# CE_BJTInfineonTSFP-4-1_v1.net
KiCad netlist of a schematic drawn in Altium Designer
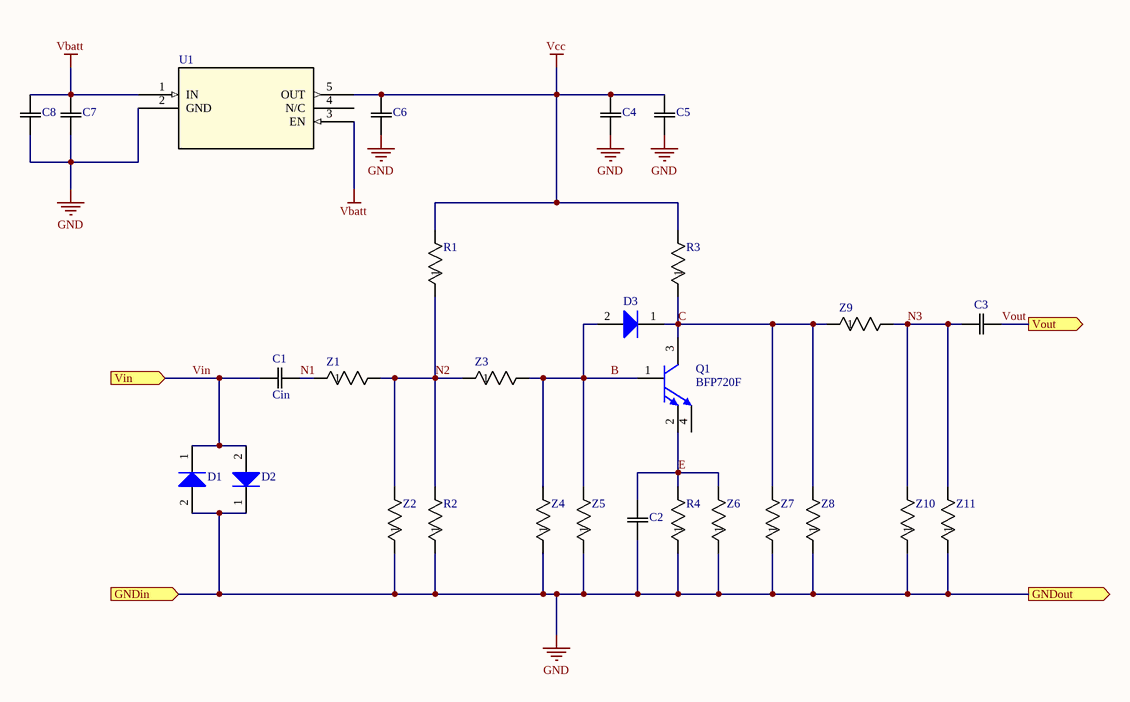
[diagram p0: CE_BJTInfineonTSFP-4-1_v1.SchDoc]

(export (version "E")
  (design (tool "Eeschema 10.0.6"))
  (components
    (comp (ref "C1")
      (value "Cin")
      (footprint "C0201")
      (description "No Description Available")
      (fields
        (field (name "MANUFACTURER_PART_NUMBER") "C0201C270J3GACTU")
        (field (name "COPYRIGHT") "Copyright (C) 2018 Accelerated Designs. All rights reserved")
      )
      (libsource (lib "0201Capacitor_Yageo") (part "C0201C270J3GACTU"))
    )
    (comp (ref "C2")
      (value "~")
      (footprint "C0201")
      (description "No Description Available")
      (fields
        (field (name "MANUFACTURER_PART_NUMBER") "C0201C270J3GACTU")
        (field (name "COPYRIGHT") "Copyright (C) 2018 Accelerated Designs. All rights reserved")
      )
      (libsource (lib "0201Capacitor_Yageo") (part "C0201C270J3GACTU"))
    )
    (comp (ref "C3")
      (value "~")
      (footprint "C0201")
      (description "No Description Available")
      (fields
        (field (name "MANUFACTURER_PART_NUMBER") "C0201C270J3GACTU")
        (field (name "COPYRIGHT") "Copyright (C) 2018 Accelerated Designs. All rights reserved")
      )
      (libsource (lib "0201Capacitor_Yageo") (part "C0201C270J3GACTU"))
    )
    (comp (ref "C4")
      (value "~")
      (footprint "CAP_CBR_0201")
      (description "No Description Available")
      (fields
        (field (name "MANUFACTURER_PART_NUMBER") "CBR02C399C3GAC")
        (field (name "COPYRIGHT") "Copyright (C) 2018 Accelerated Designs. All rights reserved")
      )
      (libsource (lib "0201Capacitor_KEMET") (part "CBR02C399C3GAC"))
    )
    (comp (ref "C5")
      (value "~")
      (footprint "CAP_CBR_0201")
      (description "No Description Available")
      (fields
        (field (name "MANUFACTURER_PART_NUMBER") "CBR02C399C3GAC")
        (field (name "COPYRIGHT") "Copyright (C) 2018 Accelerated Designs. All rights reserved")
      )
      (libsource (lib "0201Capacitor_KEMET") (part "CBR02C399C3GAC"))
    )
    (comp (ref "C6")
      (value "~")
      (footprint "YAG_CC0402")
      (description "No Description Available")
      (fields
        (field (name "MANUFACTURER_PART_NUMBER") "CC0402KRX7R9BB103")
        (field (name "COPYRIGHT") "Copyright (C) 2018 Accelerated Designs. All rights reserved")
      )
      (libsource (lib "0402Capacitor_Yageo") (part "CC0402KRX7R9BB10"))
    )
    (comp (ref "C7")
      (value "~")
      (footprint "YAG_CC0402")
      (description "No Description Available")
      (fields
        (field (name "MANUFACTURER_PART_NUMBER") "CC0402KRX7R9BB103")
        (field (name "COPYRIGHT") "Copyright (C) 2018 Accelerated Designs. All rights reserved")
      )
      (libsource (lib "0402Capacitor_Yageo") (part "CC0402KRX7R9BB10"))
    )
    (comp (ref "C8")
      (value "~")
      (footprint "YAG_CC0402")
      (description "No Description Available")
      (fields
        (field (name "MANUFACTURER_PART_NUMBER") "CC0402KRX7R9BB103")
        (field (name "COPYRIGHT") "Copyright (C) 2018 Accelerated Designs. All rights reserved")
      )
      (libsource (lib "0402Capacitor_Yageo") (part "CC0402KRX7R9BB10"))
    )
    (comp (ref "D1")
      (value "~")
      (footprint "INF-SOD323_V")
      (description "Single Silicon Schottky Diode, 110 mA IF Max, SOD32, Green")
      (fields (field (name "MANUFACTURER") "Infineon") (field (name "PARTNUMBER") "BAT15-03W"))
      (libsource (lib "Infineon_RFSchottkyDiode_SOD323") (part "BAT15-03W"))
    )
    (comp (ref "D2")
      (value "~")
      (footprint "INF-SOD323_V")
      (description "Single Silicon Schottky Diode, 110 mA IF Max, SOD32, Green")
      (fields (field (name "MANUFACTURER") "Infineon") (field (name "PARTNUMBER") "BAT15-03W"))
      (libsource (lib "Infineon_RFSchottkyDiode_SOD323") (part "BAT15-03W"))
    )
    (comp (ref "D3")
      (value "~")
      (footprint "INF-SOD323_V")
      (description "Single Silicon Schottky Diode, 110 mA IF Max, SOD32, Green")
      (fields (field (name "MANUFACTURER") "Infineon") (field (name "PARTNUMBER") "BAT15-03W"))
      (libsource (lib "Infineon_RFSchottkyDiode_SOD323") (part "BAT15-03W"))
    )
    (comp (ref "Q1")
      (value "BFP720F")
      (footprint "INF-TSFP-4-1_V")
      (fields (field (name "MANUFACTURER") "Infineon"))
      (libsource (lib "Infineon_RFBJT_TSFP-4-1") (part "BFP720F"))
    )
    (comp (ref "R1")
      (value "~")
      (footprint "RES_RC0201_P6XP3")
      (description "No Description Available")
      (fields
        (field (name "MANUFACTURER_PART_NUMBER") "RC0201FR-0718KL")
        (field (name "COPYRIGHT") "Copyright (C) 2018 Accelerated Designs. All rights reserved")
      )
      (libsource (lib "0201Resistor_Yageo") (part "RC0201FR-0718KL"))
    )
    (comp (ref "R2")
      (value "~")
      (footprint "RES_RC0201_P6XP3")
      (description "No Description Available")
      (fields
        (field (name "MANUFACTURER_PART_NUMBER") "RC0201FR-0718KL")
        (field (name "COPYRIGHT") "Copyright (C) 2018 Accelerated Designs. All rights reserved")
      )
      (libsource (lib "0201Resistor_Yageo") (part "RC0201FR-0718KL"))
    )
    (comp (ref "R3")
      (value "~")
      (footprint "RES_RC0201_P6XP3")
      (description "No Description Available")
      (fields
        (field (name "MANUFACTURER_PART_NUMBER") "RC0201FR-0718KL")
        (field (name "COPYRIGHT") "Copyright (C) 2018 Accelerated Designs. All rights reserved")
      )
      (libsource (lib "0201Resistor_Yageo") (part "RC0201FR-0718KL"))
    )
    (comp (ref "R4")
      (value "~")
      (footprint "RES_RC0201_P6XP3")
      (description "No Description Available")
      (fields
        (field (name "MANUFACTURER_PART_NUMBER") "RC0201FR-0718KL")
        (field (name "COPYRIGHT") "Copyright (C) 2018 Accelerated Designs. All rights reserved")
      )
      (libsource (lib "0201Resistor_Yageo") (part "RC0201FR-0718KL"))
    )
    (comp (ref "U1")
      (value "~")
      (footprint "DBV5")
      (description "No Description Available")
      (fields
        (field (name "MANUFACTURER_PART_NUMBER") "LP5907MFX-3.3/NOPB")
        (field (name "COPYRIGHT") "Copyright (C) 2018 Accelerated Designs. All rights reserved")
      )
      (libsource (lib "TI_LDO_3V3_SOT325") (part "LP5907MFX-3.3/NO"))
    )
    (comp (ref "Z1")
      (value "~")
      (footprint "RES_RC0201_P6XP3")
      (description "No Description Available")
      (fields
        (field (name "MANUFACTURER_PART_NUMBER") "RC0201FR-0718KL")
        (field (name "COPYRIGHT") "Copyright (C) 2018 Accelerated Designs. All rights reserved")
      )
      (libsource (lib "0201Resistor_Yageo") (part "RC0201FR-0718KL"))
    )
    (comp (ref "Z2")
      (value "~")
      (footprint "RES_RC0201_P6XP3")
      (description "No Description Available")
      (fields
        (field (name "MANUFACTURER_PART_NUMBER") "RC0201FR-0718KL")
        (field (name "COPYRIGHT") "Copyright (C) 2018 Accelerated Designs. All rights reserved")
      )
      (libsource (lib "0201Resistor_Yageo") (part "RC0201FR-0718KL"))
    )
    (comp (ref "Z3")
      (value "~")
      (footprint "RES_RC0201_P6XP3")
      (description "No Description Available")
      (fields
        (field (name "MANUFACTURER_PART_NUMBER") "RC0201FR-0718KL")
        (field (name "COPYRIGHT") "Copyright (C) 2018 Accelerated Designs. All rights reserved")
      )
      (libsource (lib "0201Resistor_Yageo") (part "RC0201FR-0718KL"))
    )
    (comp (ref "Z4")
      (value "~")
      (footprint "RES_RC0201_P6XP3")
      (description "No Description Available")
      (fields
        (field (name "MANUFACTURER_PART_NUMBER") "RC0201FR-0718KL")
        (field (name "COPYRIGHT") "Copyright (C) 2018 Accelerated Designs. All rights reserved")
      )
      (libsource (lib "0201Resistor_Yageo") (part "RC0201FR-0718KL"))
    )
    (comp (ref "Z5")
      (value "~")
      (footprint "RES_RC0201_P6XP3")
      (description "No Description Available")
      (fields
        (field (name "MANUFACTURER_PART_NUMBER") "RC0201FR-0718KL")
        (field (name "COPYRIGHT") "Copyright (C) 2018 Accelerated Designs. All rights reserved")
      )
      (libsource (lib "0201Resistor_Yageo") (part "RC0201FR-0718KL"))
    )
    (comp (ref "Z6")
      (value "~")
      (footprint "RES_RC0201_P6XP3")
      (description "No Description Available")
      (fields
        (field (name "MANUFACTURER_PART_NUMBER") "RC0201FR-0718KL")
        (field (name "COPYRIGHT") "Copyright (C) 2018 Accelerated Designs. All rights reserved")
      )
      (libsource (lib "0201Resistor_Yageo") (part "RC0201FR-0718KL"))
    )
    (comp (ref "Z7")
      (value "~")
      (footprint "RES_RC0201_P6XP3")
      (description "No Description Available")
      (fields
        (field (name "MANUFACTURER_PART_NUMBER") "RC0201FR-0718KL")
        (field (name "COPYRIGHT") "Copyright (C) 2018 Accelerated Designs. All rights reserved")
      )
      (libsource (lib "0201Resistor_Yageo") (part "RC0201FR-0718KL"))
    )
    (comp (ref "Z8")
      (value "~")
      (footprint "RES_RC0201_P6XP3")
      (description "No Description Available")
      (fields
        (field (name "MANUFACTURER_PART_NUMBER") "RC0201FR-0718KL")
        (field (name "COPYRIGHT") "Copyright (C) 2018 Accelerated Designs. All rights reserved")
      )
      (libsource (lib "0201Resistor_Yageo") (part "RC0201FR-0718KL"))
    )
    (comp (ref "Z9")
      (value "~")
      (footprint "RES_RC0201_P6XP3")
      (description "No Description Available")
      (fields
        (field (name "MANUFACTURER_PART_NUMBER") "RC0201FR-0718KL")
        (field (name "COPYRIGHT") "Copyright (C) 2018 Accelerated Designs. All rights reserved")
      )
      (libsource (lib "0201Resistor_Yageo") (part "RC0201FR-0718KL"))
    )
    (comp (ref "Z10")
      (value "~")
      (footprint "RES_RC0201_P6XP3")
      (description "No Description Available")
      (fields
        (field (name "MANUFACTURER_PART_NUMBER") "RC0201FR-0718KL")
        (field (name "COPYRIGHT") "Copyright (C) 2018 Accelerated Designs. All rights reserved")
      )
      (libsource (lib "0201Resistor_Yageo") (part "RC0201FR-0718KL"))
    )
    (comp (ref "Z11")
      (value "~")
      (footprint "RES_RC0201_P6XP3")
      (description "No Description Available")
      (fields
        (field (name "MANUFACTURER_PART_NUMBER") "RC0201FR-0718KL")
        (field (name "COPYRIGHT") "Copyright (C) 2018 Accelerated Designs. All rights reserved")
      )
      (libsource (lib "0201Resistor_Yageo") (part "RC0201FR-0718KL"))
    )
  )
  (nets
    (net (code "1") (name "/B") (class "Default")
      (node (ref "D3") (pin "2") (pinfunction "A_2") (pintype "passive"))
      (node (ref "Q1") (pin "1") (pinfunction "B_1") (pintype "passive"))
      (node (ref "Z3") (pin "2") (pinfunction "2_2") (pintype "passive"))
      (node (ref "Z4") (pin "2") (pinfunction "2_2") (pintype "passive"))
      (node (ref "Z5") (pin "2") (pinfunction "2_2") (pintype "passive"))
    )
    (net (code "2") (name "/C") (class "Default")
      (node (ref "D3") (pin "1") (pinfunction "K_1") (pintype "passive"))
      (node (ref "Q1") (pin "3") (pinfunction "C_3") (pintype "passive"))
      (node (ref "R3") (pin "1") (pinfunction "1_1") (pintype "passive"))
      (node (ref "Z7") (pin "2") (pinfunction "2_2") (pintype "passive"))
      (node (ref "Z8") (pin "2") (pinfunction "2_2") (pintype "passive"))
      (node (ref "Z9") (pin "1") (pinfunction "1_1") (pintype "passive"))
    )
    (net (code "3") (name "/E") (class "Default")
      (node (ref "C2") (pin "2") (pinfunction "2_2") (pintype "passive"))
      (node (ref "Q1") (pin "2") (pinfunction "E_2") (pintype "passive"))
      (node (ref "R4") (pin "2") (pinfunction "2_2") (pintype "passive"))
      (node (ref "Z6") (pin "2") (pinfunction "2_2") (pintype "passive"))
    )
    (net (code "4") (name "/N1") (class "Default")
      (node (ref "C1") (pin "2") (pinfunction "2_2") (pintype "passive"))
      (node (ref "Z1") (pin "1") (pinfunction "1_1") (pintype "passive"))
    )
    (net (code "5") (name "/N2") (class "Default")
      (node (ref "R1") (pin "1") (pinfunction "1_1") (pintype "passive"))
      (node (ref "R2") (pin "2") (pinfunction "2_2") (pintype "passive"))
      (node (ref "Z1") (pin "2") (pinfunction "2_2") (pintype "passive"))
      (node (ref "Z2") (pin "2") (pinfunction "2_2") (pintype "passive"))
      (node (ref "Z3") (pin "1") (pinfunction "1_1") (pintype "passive"))
    )
    (net (code "6") (name "/N3") (class "Default")
      (node (ref "C3") (pin "1") (pinfunction "1_1") (pintype "passive"))
      (node (ref "Z10") (pin "2") (pinfunction "2_2") (pintype "passive"))
      (node (ref "Z11") (pin "2") (pinfunction "2_2") (pintype "passive"))
      (node (ref "Z9") (pin "2") (pinfunction "2_2") (pintype "passive"))
    )
    (net (code "7") (name "/Vin") (class "Default")
      (node (ref "C1") (pin "1") (pinfunction "1_1") (pintype "passive"))
      (node (ref "D1") (pin "1") (pinfunction "K_1") (pintype "passive"))
      (node (ref "D2") (pin "2") (pinfunction "A_2") (pintype "passive"))
    )
    (net (code "8") (name "/Vout") (class "Default")
      (node (ref "C3") (pin "2") (pinfunction "2_2") (pintype "passive"))
    )
    (net (code "9") (name "GND") (class "Default")
      (node (ref "C2") (pin "1") (pinfunction "1_1") (pintype "passive"))
      (node (ref "C4") (pin "1") (pinfunction "1_1") (pintype "passive"))
      (node (ref "C5") (pin "1") (pinfunction "1_1") (pintype "passive"))
      (node (ref "C6") (pin "1") (pinfunction "1_1") (pintype "passive"))
      (node (ref "C7") (pin "1") (pinfunction "1_1") (pintype "passive"))
      (node (ref "C8") (pin "1") (pinfunction "1_1") (pintype "passive"))
      (node (ref "D1") (pin "2") (pinfunction "A_2") (pintype "passive"))
      (node (ref "D2") (pin "1") (pinfunction "K_1") (pintype "passive"))
      (node (ref "R2") (pin "1") (pinfunction "1_1") (pintype "passive"))
      (node (ref "R4") (pin "1") (pinfunction "1_1") (pintype "passive"))
      (node (ref "U1") (pin "2") (pinfunction "GND_2") (pintype "power_in"))
      (node (ref "Z10") (pin "1") (pinfunction "1_1") (pintype "passive"))
      (node (ref "Z11") (pin "1") (pinfunction "1_1") (pintype "passive"))
      (node (ref "Z2") (pin "1") (pinfunction "1_1") (pintype "passive"))
      (node (ref "Z4") (pin "1") (pinfunction "1_1") (pintype "passive"))
      (node (ref "Z5") (pin "1") (pinfunction "1_1") (pintype "passive"))
      (node (ref "Z6") (pin "1") (pinfunction "1_1") (pintype "passive"))
      (node (ref "Z7") (pin "1") (pinfunction "1_1") (pintype "passive"))
      (node (ref "Z8") (pin "1") (pinfunction "1_1") (pintype "passive"))
    )
    (net (code "10") (name "Vbatt") (class "Default")
      (node (ref "C7") (pin "2") (pinfunction "2_2") (pintype "passive"))
      (node (ref "C8") (pin "2") (pinfunction "2_2") (pintype "passive"))
      (node (ref "U1") (pin "1") (pinfunction "IN_1") (pintype "input"))
      (node (ref "U1") (pin "3") (pinfunction "EN_3") (pintype "input"))
    )
    (net (code "11") (name "Vcc") (class "Default")
      (node (ref "C4") (pin "2") (pinfunction "2_2") (pintype "passive"))
      (node (ref "C5") (pin "2") (pinfunction "2_2") (pintype "passive"))
      (node (ref "C6") (pin "2") (pinfunction "2_2") (pintype "passive"))
      (node (ref "R1") (pin "2") (pinfunction "2_2") (pintype "passive"))
      (node (ref "R3") (pin "2") (pinfunction "2_2") (pintype "passive"))
      (node (ref "U1") (pin "5") (pinfunction "OUT_5") (pintype "output"))
    )
    (net (code "12") (name "unconnected-(Q1-E-Pad4)") (class "Default")
      (node (ref "Q1") (pin "4") (pinfunction "E_4") (pintype "passive"))
    )
    (net (code "13") (name "unconnected-(U1-N{slash}C-Pad4)") (class "Default")
      (node (ref "U1") (pin "4") (pinfunction "N/C_4") (pintype "passive"))
    )
  )
)
